# Max942.net
KiCad netlist of a schematic drawn in Altium Designer
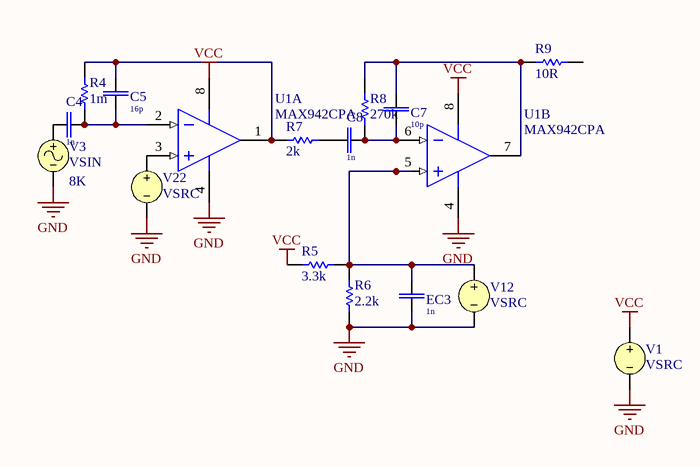
[diagram p0: Max942.SchDoc]

(export (version "E")
  (design (tool "Eeschema 10.0.6"))
  (components
    (comp (ref "C4")
      (value "1n")
      (description "Capacitor")
      (fields (field (name "Comment") "Cap") (field (name "PUBLISHER") "Altium Limited"))
      (libsource (lib "Miscellaneous Devices") (part "Cap"))
    )
    (comp (ref "C5")
      (value "16p")
      (description "Capacitor")
      (fields (field (name "Comment") "Cap") (field (name "PUBLISHER") "Altium Limited"))
      (libsource (lib "Miscellaneous Devices") (part "Cap"))
    )
    (comp (ref "C7")
      (value "10p")
      (description "Capacitor")
      (fields (field (name "Comment") "Cap") (field (name "PUBLISHER") "Altium Limited"))
      (libsource (lib "Miscellaneous Devices") (part "Cap"))
    )
    (comp (ref "C8")
      (value "1n")
      (description "Capacitor")
      (fields (field (name "Comment") "Cap") (field (name "PUBLISHER") "Altium Limited"))
      (libsource (lib "Miscellaneous Devices") (part "Cap"))
    )
    (comp (ref "EC3")
      (value "1n")
      (description "Capacitor")
      (fields (field (name "Comment") "Cap") (field (name "PUBLISHER") "Altium Limited"))
      (libsource (lib "Miscellaneous Devices") (part "Cap"))
    )
    (comp (ref "R4")
      (value "1m")
      (footprint "AXIAL-0.5")
      (description "Semiconductor Resistor")
      (fields (field (name "Comment") "Res Semi") (field (name "PUBLISHER") "Altium Limited"))
      (libsource (lib "Miscellaneous Devices") (part "Res Semi"))
    )
    (comp (ref "R5")
      (value "3.3k")
      (footprint "AXIAL-0.5")
      (description "Semiconductor Resistor")
      (fields (field (name "Comment") "Res Semi") (field (name "PUBLISHER") "Altium Limited"))
      (libsource (lib "Miscellaneous Devices") (part "Res Semi"))
    )
    (comp (ref "R6")
      (value "2.2k")
      (footprint "AXIAL-0.5")
      (description "Semiconductor Resistor")
      (fields (field (name "Comment") "Res Semi") (field (name "PUBLISHER") "Altium Limited"))
      (libsource (lib "Miscellaneous Devices") (part "Res Semi"))
    )
    (comp (ref "R7")
      (value "2k")
      (footprint "AXIAL-0.5")
      (description "Semiconductor Resistor")
      (fields (field (name "Comment") "Res Semi") (field (name "PUBLISHER") "Altium Limited"))
      (libsource (lib "Miscellaneous Devices") (part "Res Semi"))
    )
    (comp (ref "R8")
      (value "270k")
      (footprint "AXIAL-0.5")
      (description "Semiconductor Resistor")
      (fields (field (name "Comment") "Res Semi") (field (name "PUBLISHER") "Altium Limited"))
      (libsource (lib "Miscellaneous Devices") (part "Res Semi"))
    )
    (comp (ref "R9")
      (value "10R")
      (footprint "AXIAL-0.5")
      (description "Semiconductor Resistor")
      (fields (field (name "Comment") "Res Semi") (field (name "PUBLISHER") "Altium Limited"))
      (libsource (lib "Miscellaneous Devices") (part "Res Semi"))
    )
    (comp (ref "U1")
      (value "MAX942CPA")
      (footprint "PA8")
      (description "High-speed, Low-power, 3V/5V, Rail-to-Rail Dual-Supply Comparator")
      (fields (field (name "PUBLISHER") "Altium Limited"))
      (libsource (lib "Maxim Analog Comparator") (part "MAX942CPA"))
    )
    (comp (ref "V1")
      (value "VSRC")
      (description "Voltage Source")
      (fields (field (name "PUBLISHER") "Altium Limited"))
      (libsource (lib "Simulation Sources") (part "VSRC"))
    )
    (comp (ref "V3")
      (value "VSIN")
      (description "Sinusoidal Voltage Source")
      (fields (field (name "FREQUENCY") "8K") (field (name "PUBLISHER") "Altium Limited"))
      (libsource (lib "Simulation Sources") (part "VSIN"))
    )
    (comp (ref "V12")
      (value "VSRC")
      (description "Voltage Source")
      (fields (field (name "PUBLISHER") "Altium Limited"))
      (libsource (lib "Simulation Sources") (part "VSRC"))
    )
    (comp (ref "V22")
      (value "VSRC")
      (description "Voltage Source")
      (fields (field (name "PUBLISHER") "Altium Limited"))
      (libsource (lib "Simulation Sources") (part "VSRC"))
    )
  )
  (nets
    (net (code "1") (name "GND") (class "Default")
      (node (ref "EC3") (pin "2") (pinfunction "2_2") (pintype "passive"))
      (node (ref "R6") (pin "2") (pinfunction "2_2") (pintype "passive"))
      (node (ref "U1") (pin "4") (pinfunction "GND_4") (pintype "power_in"))
      (node (ref "V1") (pin "2") (pinfunction "2_2") (pintype "passive"))
      (node (ref "V12") (pin "2") (pinfunction "2_2") (pintype "passive"))
      (node (ref "V22") (pin "2") (pinfunction "2_2") (pintype "passive"))
      (node (ref "V3") (pin "2") (pinfunction "2_2") (pintype "passive"))
    )
    (net (code "2") (name "Net-(C4-Pad1)") (class "Default")
      (node (ref "C4") (pin "1") (pinfunction "1_1") (pintype "passive"))
      (node (ref "V3") (pin "1") (pinfunction "1_1") (pintype "passive"))
    )
    (net (code "3") (name "Net-(C8-Pad2)") (class "Default")
      (node (ref "C8") (pin "2") (pinfunction "2_2") (pintype "passive"))
      (node (ref "R7") (pin "1") (pinfunction "1_1") (pintype "passive"))
    )
    (net (code "4") (name "Net-(U1A-IN+)") (class "Default")
      (node (ref "U1") (pin "3") (pinfunction "IN+_3") (pintype "input"))
      (node (ref "V22") (pin "1") (pinfunction "1_1") (pintype "passive"))
    )
    (net (code "5") (name "Net-(U1A-IN-)") (class "Default")
      (node (ref "C4") (pin "2") (pinfunction "2_2") (pintype "passive"))
      (node (ref "C5") (pin "1") (pinfunction "1_1") (pintype "passive"))
      (node (ref "R4") (pin "1") (pinfunction "1_1") (pintype "passive"))
      (node (ref "U1") (pin "2") (pinfunction "IN-_2") (pintype "input"))
    )
    (net (code "6") (name "Net-(U1A-OUT)") (class "Default")
      (node (ref "C5") (pin "2") (pinfunction "2_2") (pintype "passive"))
      (node (ref "R4") (pin "2") (pinfunction "2_2") (pintype "passive"))
      (node (ref "R7") (pin "2") (pinfunction "2_2") (pintype "passive"))
      (node (ref "U1") (pin "1") (pinfunction "OUT_1") (pintype "tri_state"))
    )
    (net (code "7") (name "Net-(U1B-IN+)") (class "Default")
      (node (ref "EC3") (pin "1") (pinfunction "1_1") (pintype "passive"))
      (node (ref "R5") (pin "2") (pinfunction "2_2") (pintype "passive"))
      (node (ref "R6") (pin "1") (pinfunction "1_1") (pintype "passive"))
      (node (ref "U1") (pin "5") (pinfunction "IN+_5") (pintype "input"))
      (node (ref "V12") (pin "1") (pinfunction "1_1") (pintype "passive"))
    )
    (net (code "8") (name "Net-(U1B-IN-)") (class "Default")
      (node (ref "C7") (pin "2") (pinfunction "2_2") (pintype "passive"))
      (node (ref "C8") (pin "1") (pinfunction "1_1") (pintype "passive"))
      (node (ref "R8") (pin "2") (pinfunction "2_2") (pintype "passive"))
      (node (ref "U1") (pin "6") (pinfunction "IN-_6") (pintype "input"))
    )
    (net (code "9") (name "Net-(U1B-OUT)") (class "Default")
      (node (ref "C7") (pin "1") (pinfunction "1_1") (pintype "passive"))
      (node (ref "R8") (pin "1") (pinfunction "1_1") (pintype "passive"))
      (node (ref "R9") (pin "2") (pinfunction "2_2") (pintype "passive"))
      (node (ref "U1") (pin "7") (pinfunction "OUT_7") (pintype "tri_state"))
    )
    (net (code "10") (name "VCC") (class "Default")
      (node (ref "R5") (pin "1") (pinfunction "1_1") (pintype "passive"))
      (node (ref "U1") (pin "8") (pinfunction "V+_8") (pintype "power_in"))
      (node (ref "V1") (pin "1") (pinfunction "1_1") (pintype "passive"))
    )
    (net (code "11") (name "unconnected-(R9-Pad1)") (class "Default")
      (node (ref "R9") (pin "1") (pinfunction "1_1") (pintype "passive"))
    )
  )
)
